# measurement_ch0.net
KiCad netlist of a schematic drawn in Altium Designer
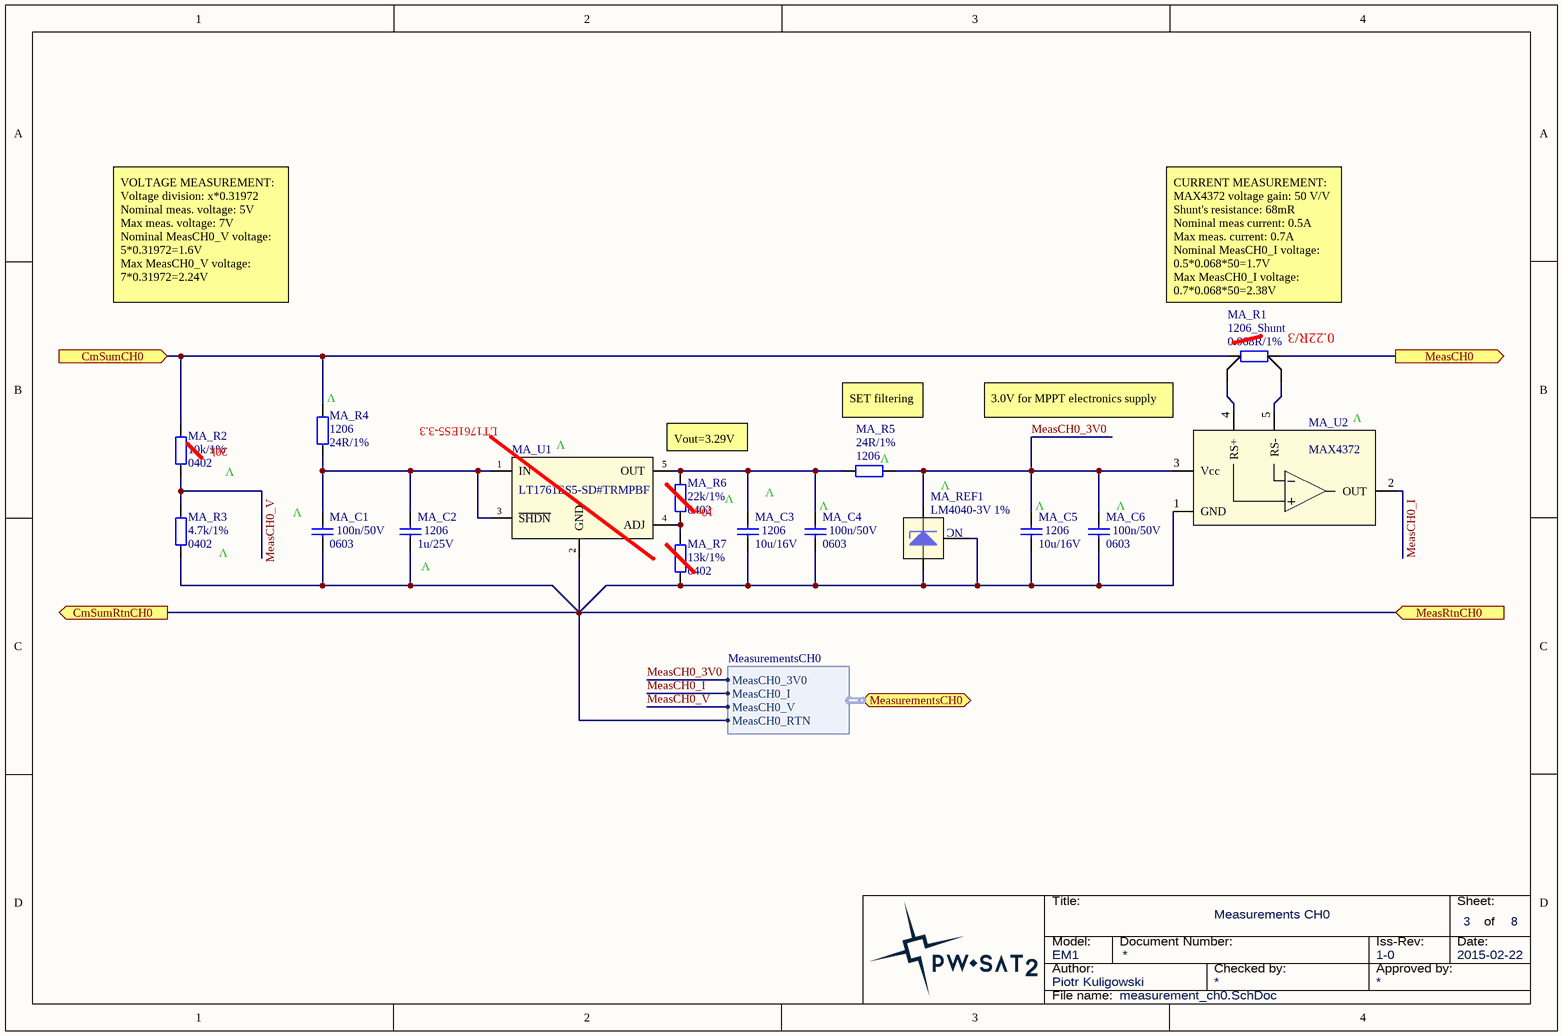
[diagram p0: measurement_ch0.SchDoc]

(export (version "E")
  (design (tool "Eeschema 10.0.6"))
  (components
    (comp (ref "MA_C1")
      (value "100n/50V")
      (footprint "SMD_Capacitor_0603")
      (description "Ceramic Cap Kemet COTS 100n/50V X7R 0603")
      (fields
        (field (name "MANUFACTURER") "Kemet")
        (field (name "MANUFACTURERPARTNUMBER") "C0603T104K5RALTU")
        (field (name "PACKAGE") "0603")
      )
      (libsource (lib "capacitors") (part "Cer_C0603T104K5RALTU"))
    )
    (comp (ref "MA_C2")
      (value "1u/25V")
      (footprint "SMD_Capacitor_1206")
      (description "Ceramic Cap Kemet COTS 1u/25V X7R 1206")
      (fields
        (field (name "MANUFACTURERPARTNUMBER") "C1206T105K3RALTU")
        (field (name "MANUFACTURER") "Kemet")
        (field (name "PACKAGE") "1206")
      )
      (libsource (lib "capacitors") (part "Cer_C1206T105K3RALTU"))
    )
    (comp (ref "MA_C3")
      (value "10u/16V")
      (footprint "SMD_Capacitor_1206")
      (description "Ceramic Cap Kemet COTS 10u/16V X7R 1206")
      (fields
        (field (name "MANUFACTURERPARTNUMBER") "C1206T106K4RACTU")
        (field (name "MANUFACTURER") "Kemet")
        (field (name "PACKGE") "1206")
      )
      (libsource (lib "capacitors") (part "Cer_C1206T106K4RACTU"))
    )
    (comp (ref "MA_C4")
      (value "100n/50V")
      (footprint "SMD_Capacitor_0603")
      (description "Ceramic Cap Kemet COTS 100n/50V X7R 0603")
      (fields
        (field (name "MANUFACTURER") "Kemet")
        (field (name "MANUFACTURERPARTNUMBER") "C0603T104K5RALTU")
        (field (name "PACKAGE") "0603")
      )
      (libsource (lib "capacitors") (part "Cer_C0603T104K5RALTU"))
    )
    (comp (ref "MA_C5")
      (value "10u/16V")
      (footprint "SMD_Capacitor_1206")
      (description "Ceramic Cap Kemet COTS 10u/16V X7R 1206")
      (fields
        (field (name "MANUFACTURERPARTNUMBER") "C1206T106K4RACTU")
        (field (name "MANUFACTURER") "Kemet")
        (field (name "PACKGE") "1206")
      )
      (libsource (lib "capacitors") (part "Cer_C1206T106K4RACTU"))
    )
    (comp (ref "MA_C6")
      (value "100n/50V")
      (footprint "SMD_Capacitor_0603")
      (description "Ceramic Cap Kemet COTS 100n/50V X7R 0603")
      (fields
        (field (name "MANUFACTURER") "Kemet")
        (field (name "MANUFACTURERPARTNUMBER") "C0603T104K5RALTU")
        (field (name "PACKAGE") "0603")
      )
      (libsource (lib "capacitors") (part "Cer_C0603T104K5RALTU"))
    )
    (comp (ref "MA_R1")
      (value "0.068R/1%")
      (footprint "SMD_Resistor-Shunt_1206")
      (description "Panasonic Resistor 68mR 1% 1206 1W")
      (fields
        (field (name "MANUFACTURER") "Panasonic")
        (field (name "MANUFACTURERPARTNUMBER") "ERJ-8BWFR068V")
        (field (name "PACKAGE") "1206_Shunt")
      )
      (libsource (lib "resistors") (part "ERJ-8BWFR068V"))
    )
    (comp (ref "MA_R2")
      (value "10k/1%")
      (footprint "SMD_Resistor_0402")
      (description "10k/1% Vishay CRCW 0402 Resistor. 63mW, 100ppm, 50V.")
      (fields
        (field (name "MANUFACTURER") "Vishay")
        (field (name "MANUFACTURERPARTNUMBER") "CRCW040210K0FKxxxx")
        (field (name "PACKAGE") "0402")
      )
      (libsource (lib "resistors") (part "CRCW040210K0FKxxxx"))
    )
    (comp (ref "MA_R3")
      (value "4.7k/1%")
      (footprint "SMD_Resistor_0402")
      (description "4.7k/1% Vishay CRCW 0402 Resistor. 63mW, 100ppm, 50V.")
      (fields
        (field (name "MANUFACTURERPARTNUMBER") "CRCW04024K70FKxxxx")
        (field (name "MANUFACTURER") "Vishay")
        (field (name "PACKAGE") "0402")
      )
      (libsource (lib "resistors") (part "CRCW04024K70FKxxxx"))
    )
    (comp (ref "MA_R4")
      (value "24R/1%")
      (footprint "SMD_Resistor_1206")
      (description "24R/1% Vishay CRCW 1206 Resistor. 250mW, 100ppm, 200V.")
      (fields
        (field (name "MANUFACTURERPARTNUMBER") "CRCW120624R0FKxxxx")
        (field (name "MANUFACTURER") "Vishay")
        (field (name "PACKAGE") "1206")
      )
      (libsource (lib "") (part "CRCW120624R0FKxxxx_1"))
    )
    (comp (ref "MA_R5")
      (value "24R/1%")
      (footprint "SMD_Resistor_1206")
      (description "24R/1% Vishay CRCW 1206 Resistor. 250mW, 100ppm, 200V.")
      (fields
        (field (name "MANUFACTURERPARTNUMBER") "CRCW120624R0FKxxxx")
        (field (name "MANUFACTURER") "Vishay")
        (field (name "PACKAGE") "1206")
      )
      (libsource (lib "resistors") (part "CRCW120624R0FKxxxx"))
    )
    (comp (ref "MA_R6")
      (value "22k/1%")
      (footprint "SMD_Resistor_0402")
      (description "22k/1% Vishay CRCW 0402 Resistor. 63mW, 100ppm, 50V.")
      (fields
        (field (name "MANUFACTURER") "Vishay")
        (field (name "MANUFACTURERPARTNUMBER") "CRCW040222K0FKxxxx")
        (field (name "PACKAGE") "0402")
      )
      (libsource (lib "resistors") (part "CRCW040222K0FKxxxx"))
    )
    (comp (ref "MA_R7")
      (value "13k/1%")
      (footprint "SMD_Resistor_0402")
      (description "13k/1% Vishay CRCW 0402 Resistor. 63mW, 100ppm, 50V.")
      (fields
        (field (name "MANUFACTURERPARTNUMBER") "CRCW040213K0FKxxxx")
        (field (name "MANUFACTURER") "Vishay")
        (field (name "PACKAGE") "0402")
      )
      (libsource (lib "resistors") (part "CRCW040213K0FKxxxx"))
    )
    (comp (ref "MA_REF1")
      (value "LM4040-3V 1%")
      (footprint "SOT23-3")
      (description "Shunt V-REF, 3V, 1%, SOT23-3")
      (fields
        (field (name "MANUFACTURERPARTNUMBER") "LM4040DIM3-3.0")
        (field (name "MANUFACTURER") "Texas Instruments")
      )
      (libsource (lib "diodes") (part "LM4040DIM3-3.0"))
    )
    (comp (ref "MA_U1")
      (value "LT1761ES5-SD#TRMPBF")
      (footprint "SOT23-5")
      (description "100mA, Regulated, Low Noise, LDO Micropower Regulator in TSOT-23")
      (fields (field (name "MANUFACTURER") "Linear Technology"))
      (libsource (lib "microcircuits") (part "LT1761ES5-SD#TRMPBF"))
    )
    (comp (ref "MA_U2")
      (value "MAX4372")
      (footprint "SOT23-5")
      (description "High-Side Current-Sense Amplifier with Voltage Output")
      (fields (field (name "MANUFACTURER") "Maxim Integrated Products"))
      (libsource (lib "microcircuits") (part "MAX4372"))
    )
  )
  (nets
    (net (code "2") (name "/CmSumCH0") (class "Default")
      (node (ref "MA_R1") (pin "1") (pinfunction "1_1") (pintype "passive"))
      (node (ref "MA_R2") (pin "1") (pinfunction "1_1") (pintype "passive"))
      (node (ref "MA_R4") (pin "1") (pinfunction "1_1") (pintype "passive"))
    )
    (net (code "3") (name "/CmSumRtnCH0") (class "Default")
      (node (ref "MA_C1") (pin "2") (pinfunction "2_2") (pintype "passive"))
      (node (ref "MA_C2") (pin "2") (pinfunction "2_2") (pintype "passive"))
      (node (ref "MA_C3") (pin "2") (pinfunction "2_2") (pintype "passive"))
      (node (ref "MA_C4") (pin "2") (pinfunction "2_2") (pintype "passive"))
      (node (ref "MA_C5") (pin "2") (pinfunction "2_2") (pintype "passive"))
      (node (ref "MA_C6") (pin "2") (pinfunction "2_2") (pintype "passive"))
      (node (ref "MA_R3") (pin "2") (pinfunction "2_2") (pintype "passive"))
      (node (ref "MA_R7") (pin "2") (pinfunction "2_2") (pintype "passive"))
      (node (ref "MA_REF1") (pin "2") (pinfunction "A_2") (pintype "passive"))
      (node (ref "MA_REF1") (pin "3") (pinfunction "NC_3") (pintype "passive"))
      (node (ref "MA_U1") (pin "2") (pinfunction "GND_2") (pintype "passive"))
      (node (ref "MA_U2") (pin "1") (pinfunction "GND_1") (pintype "passive"))
    )
    (net (code "4") (name "/MeasCH0") (class "Default")
      (node (ref "MA_R1") (pin "4") (pinfunction "4_4") (pintype "passive"))
    )
    (net (code "5") (name "/MeasCH0_3V0") (class "Default")
      (node (ref "MA_C5") (pin "1") (pinfunction "1_1") (pintype "passive"))
      (node (ref "MA_C6") (pin "1") (pinfunction "1_1") (pintype "passive"))
      (node (ref "MA_R5") (pin "2") (pinfunction "2_2") (pintype "passive"))
      (node (ref "MA_REF1") (pin "1") (pinfunction "K_1") (pintype "passive"))
      (node (ref "MA_U2") (pin "3") (pinfunction "Vcc_3") (pintype "passive"))
    )
    (net (code "6") (name "/MeasCH0_I") (class "Default")
      (node (ref "MA_U2") (pin "2") (pinfunction "OUT_2") (pintype "passive"))
    )
    (net (code "7") (name "/MeasCH0_V") (class "Default")
      (node (ref "MA_R2") (pin "2") (pinfunction "2_2") (pintype "passive"))
      (node (ref "MA_R3") (pin "1") (pinfunction "1_1") (pintype "passive"))
    )
    (net (code "9") (name "Net-(MA_U1-ADJ)") (class "Default")
      (node (ref "MA_R6") (pin "2") (pinfunction "2_2") (pintype "passive"))
      (node (ref "MA_R7") (pin "1") (pinfunction "1_1") (pintype "passive"))
      (node (ref "MA_U1") (pin "4") (pinfunction "ADJ_4") (pintype "passive"))
    )
    (net (code "10") (name "Net-(MA_U1-IN)") (class "Default")
      (node (ref "MA_C1") (pin "1") (pinfunction "1_1") (pintype "passive"))
      (node (ref "MA_C2") (pin "1") (pinfunction "1_1") (pintype "passive"))
      (node (ref "MA_R4") (pin "2") (pinfunction "2_2") (pintype "passive"))
      (node (ref "MA_U1") (pin "1") (pinfunction "IN_1") (pintype "passive"))
      (node (ref "MA_U1") (pin "3") (pinfunction "~{SHDN}_3") (pintype "passive"))
    )
    (net (code "11") (name "Net-(MA_U1-OUT)") (class "Default")
      (node (ref "MA_C3") (pin "1") (pinfunction "1_1") (pintype "passive"))
      (node (ref "MA_C4") (pin "1") (pinfunction "1_1") (pintype "passive"))
      (node (ref "MA_R5") (pin "1") (pinfunction "1_1") (pintype "passive"))
      (node (ref "MA_R6") (pin "1") (pinfunction "1_1") (pintype "passive"))
      (node (ref "MA_U1") (pin "5") (pinfunction "OUT_5") (pintype "passive"))
    )
    (net (code "12") (name "Net-(MA_U2-RS+)") (class "Default")
      (node (ref "MA_R1") (pin "2") (pinfunction "2_2") (pintype "passive"))
      (node (ref "MA_U2") (pin "4") (pinfunction "RS+_4") (pintype "passive"))
    )
    (net (code "13") (name "Net-(MA_U2-RS-)") (class "Default")
      (node (ref "MA_R1") (pin "3") (pinfunction "3_3") (pintype "passive"))
      (node (ref "MA_U2") (pin "5") (pinfunction "RS-_5") (pintype "passive"))
    )
  )
)
